# LCD_Disp_AIR_for3xOIL.net
KiCad netlist of a schematic drawn in EAGLE
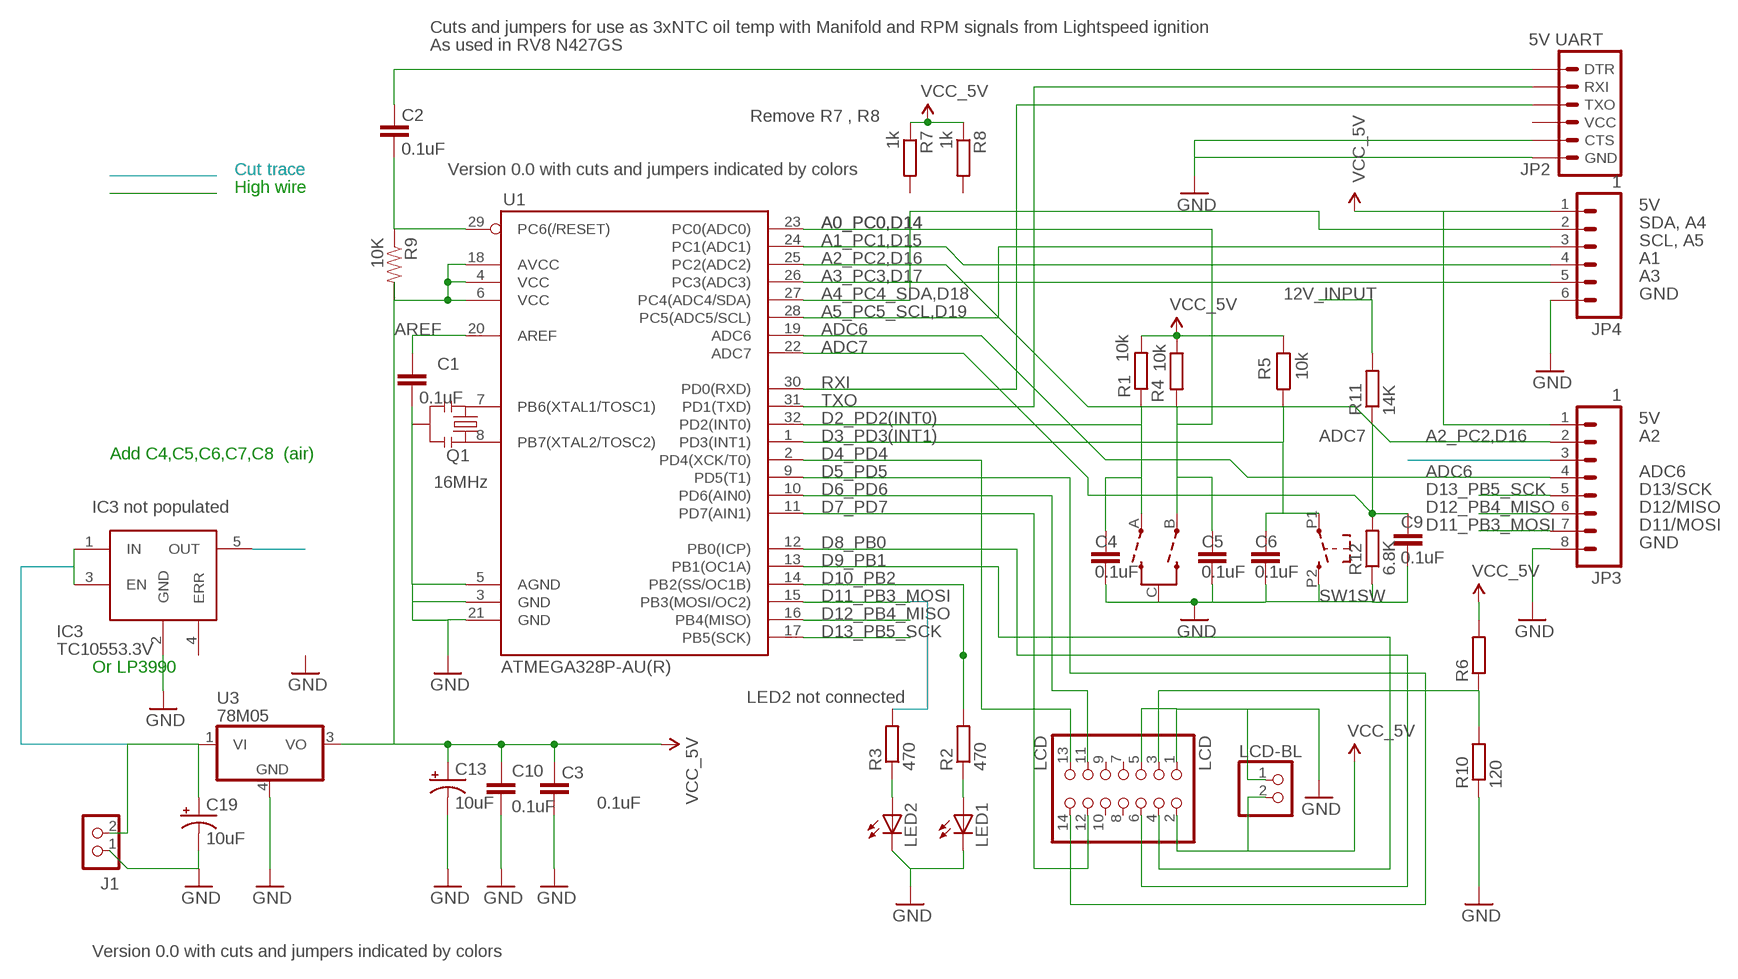
[diagram p0: schematic, sheet 1]

(export (version "E")
  (design (tool "Eeschema 10.0.6"))
  (components
    (comp (ref "C1")
      (value "0.1uF")
      (footprint "eagle-import:0805")
      (libsource (lib "eagle-import") (part "CAP0805"))
    )
    (comp (ref "C2")
      (value "0.1uF")
      (footprint "eagle-import:0805")
      (libsource (lib "eagle-import") (part "CAP0805"))
    )
    (comp (ref "C3")
      (value "0.1uF")
      (footprint "eagle-import:0805")
      (libsource (lib "eagle-import") (part "CAP0805"))
    )
    (comp (ref "C4")
      (value "0.1uF")
      (footprint "eagle-import:0805")
      (libsource (lib "eagle-import") (part "CAP0805"))
    )
    (comp (ref "C5")
      (value "0.1uF")
      (footprint "eagle-import:0805")
      (libsource (lib "eagle-import") (part "CAP0805"))
    )
    (comp (ref "C6")
      (value "0.1uF")
      (footprint "eagle-import:0805")
      (libsource (lib "eagle-import") (part "CAP0805"))
    )
    (comp (ref "C9")
      (value "0.1uF")
      (footprint "eagle-import:0805")
      (libsource (lib "eagle-import") (part "CAP0805"))
    )
    (comp (ref "C10")
      (value "0.1uF")
      (footprint "eagle-import:0805")
      (libsource (lib "eagle-import") (part "CAP0805"))
    )
    (comp (ref "C13")
      (value "10uF")
      (footprint "eagle-import:EIA3216")
      (libsource (lib "eagle-import") (part "CAP_POL1206"))
    )
    (comp (ref "C19")
      (value "10uF")
      (footprint "eagle-import:EIA7343")
      (libsource (lib "eagle-import") (part "CAP_POL7343"))
    )
    (comp (ref "IC3")
      (value "TC10553.3V")
      (footprint "eagle-import:SOT23-5")
      (libsource (lib "eagle-import") (part "TC10553.3V"))
    )
    (comp (ref "J1")
      (value "12V input")
      (footprint "eagle-import:M1X2")
      (libsource (lib "eagle-import") (part "CON_HEADER_1X02-PTH"))
    )
    (comp (ref "JP2")
      (value "5V UART")
      (footprint "eagle-import:1X06")
      (libsource (lib "eagle-import") (part "ARDUINO_SERIAL_PROGRAMPTH"))
    )
    (comp (ref "JP3")
      (value "1")
      (footprint "eagle-import:1X08")
      (libsource (lib "eagle-import") (part "M081X08"))
    )
    (comp (ref "JP4")
      (value "1")
      (footprint "eagle-import:1X06")
      (libsource (lib "eagle-import") (part "M06SIP"))
    )
    (comp (ref "LCD")
      (value "LCD")
      (footprint "eagle-import:2X07")
      (libsource (lib "eagle-import") (part "PINHD-2X7"))
    )
    (comp (ref "LCD-BL")
      (value "PINHD-1X2")
      (footprint "eagle-import:1X02")
      (libsource (lib "eagle-import") (part "PINHD-1X2"))
    )
    (comp (ref "LED1")
      (value "LED-5MM")
      (footprint "eagle-import:LED-5MM")
      (libsource (lib "eagle-import") (part "LED-5MM"))
    )
    (comp (ref "LED2")
      (value "LED-5MM")
      (footprint "eagle-import:LED-5MM")
      (libsource (lib "eagle-import") (part "LED-5MM"))
    )
    (comp (ref "Q1")
      (value "16MHz")
      (footprint "eagle-import:RESONATOR-SMD")
      (libsource (lib "eagle-import") (part "RESONATORSMD"))
    )
    (comp (ref "R1")
      (value "10k")
      (footprint "eagle-import:R603")
      (libsource (lib "eagle-import") (part "RESISTOR-0603"))
    )
    (comp (ref "R2")
      (value "470")
      (footprint "eagle-import:R603")
      (libsource (lib "eagle-import") (part "RESISTOR-0603"))
    )
    (comp (ref "R3")
      (value "470")
      (footprint "eagle-import:R603")
      (libsource (lib "eagle-import") (part "RESISTOR-0603"))
    )
    (comp (ref "R4")
      (value "10k")
      (footprint "eagle-import:R603")
      (libsource (lib "eagle-import") (part "RESISTOR-0603"))
    )
    (comp (ref "R5")
      (value "10k")
      (footprint "eagle-import:R603")
      (libsource (lib "eagle-import") (part "RESISTOR-0603"))
    )
    (comp (ref "R6")
      (value "RESISTOR-0603")
      (footprint "eagle-import:R603")
      (libsource (lib "eagle-import") (part "RESISTOR-0603"))
    )
    (comp (ref "R7")
      (value "1k")
      (footprint "eagle-import:R603")
      (libsource (lib "eagle-import") (part "RESISTOR-0603"))
    )
    (comp (ref "R8")
      (value "1k")
      (footprint "eagle-import:R603")
      (libsource (lib "eagle-import") (part "RESISTOR-0603"))
    )
    (comp (ref "R9")
      (value "10K")
      (footprint "eagle-import:0603")
      (libsource (lib "eagle-import") (part "RESISTOR0603"))
    )
    (comp (ref "R10")
      (value "120")
      (footprint "eagle-import:R603")
      (libsource (lib "eagle-import") (part "RESISTOR-0603"))
    )
    (comp (ref "R11")
      (value "14K")
      (footprint "eagle-import:R603")
      (libsource (lib "eagle-import") (part "RESISTOR-0603"))
    )
    (comp (ref "R12")
      (value "6.8K")
      (footprint "eagle-import:R603")
      (libsource (lib "eagle-import") (part "RESISTOR-0603"))
    )
    (comp (ref "SW1")
      (value "ENCODER_SW1-PEC12")
      (footprint "eagle-import:PEC12_INCREMENTAL_ENCODER")
      (libsource (lib "eagle-import") (part "ENCODER_SW1-PEC12"))
    )
    (comp (ref "U1")
      (value "ATMEGA328P-AU(R)")
      (footprint "eagle-import:TQFP32-08")
      (libsource (lib "eagle-import") (part "ATMEGA168"))
    )
    (comp (ref "U3")
      (value "78M05")
      (footprint "eagle-import:DPACK")
      (libsource (lib "eagle-import") (part "78MXXL"))
    )
  )
  (nets
    (net (code "1") (name "/12V_INPUT") (class "Default")
      (node (ref "C19") (pin "A") (pinfunction "+_A") (pintype "passive"))
      (node (ref "J1") (pin "2") (pinfunction "2_2") (pintype "passive"))
      (node (ref "R11") (pin "2") (pinfunction "2_2") (pintype "passive"))
      (node (ref "U3") (pin "1") (pinfunction "VI_1") (pintype "input"))
    )
    (net (code "2") (name "/A0_PC0,D14") (class "Default")
      (node (ref "C5") (pin "2") (pinfunction "2_2") (pintype "passive"))
      (node (ref "R4") (pin "2") (pinfunction "2_2") (pintype "passive"))
      (node (ref "SW1") (pin "B") (pinfunction "B_B") (pintype "passive"))
      (node (ref "U1") (pin "23") (pinfunction "PC0(ADC0)_23") (pintype "bidirectional"))
    )
    (net (code "3") (name "/A1_PC1,D15") (class "Default")
      (node (ref "JP4") (pin "4") (pinfunction "4_4") (pintype "passive"))
      (node (ref "U1") (pin "24") (pinfunction "PC1(ADC1)_24") (pintype "bidirectional"))
    )
    (net (code "4") (name "/A2_PC2,D16") (class "Default")
      (node (ref "JP3") (pin "2") (pinfunction "2_2") (pintype "passive"))
      (node (ref "U1") (pin "25") (pinfunction "PC2(ADC2)_25") (pintype "bidirectional"))
    )
    (net (code "5") (name "/A3_PC3,D17") (class "Default")
      (node (ref "JP4") (pin "5") (pinfunction "5_5") (pintype "passive"))
      (node (ref "U1") (pin "26") (pinfunction "PC3(ADC3)_26") (pintype "bidirectional"))
    )
    (net (code "6") (name "/A4_PC4_SDA,D18") (class "Default")
      (node (ref "JP4") (pin "2") (pinfunction "2_2") (pintype "passive"))
      (node (ref "U1") (pin "27") (pinfunction "PC4(ADC4/SDA)_27") (pintype "bidirectional"))
    )
    (net (code "7") (name "/A5_PC5_SCL,D19") (class "Default")
      (node (ref "JP4") (pin "3") (pinfunction "3_3") (pintype "passive"))
      (node (ref "U1") (pin "28") (pinfunction "PC5(ADC5/SCL)_28") (pintype "bidirectional"))
    )
    (net (code "8") (name "/ADC6") (class "Default")
      (node (ref "JP3") (pin "4") (pinfunction "4_4") (pintype "passive"))
      (node (ref "U1") (pin "19") (pinfunction "ADC6_19") (pintype "bidirectional"))
    )
    (net (code "9") (name "/ADC7") (class "Default")
      (node (ref "C9") (pin "1") (pinfunction "1_1") (pintype "passive"))
      (node (ref "R11") (pin "1") (pinfunction "1_1") (pintype "passive"))
      (node (ref "R12") (pin "2") (pinfunction "2_2") (pintype "passive"))
      (node (ref "U1") (pin "22") (pinfunction "ADC7_22") (pintype "bidirectional"))
    )
    (net (code "10") (name "/AREF") (class "Default")
      (node (ref "C1") (pin "2") (pinfunction "2_2") (pintype "passive"))
      (node (ref "U1") (pin "20") (pinfunction "AREF_20") (pintype "bidirectional"))
    )
    (net (code "11") (name "/D2_PD2(INT0)") (class "Default")
      (node (ref "C4") (pin "2") (pinfunction "2_2") (pintype "passive"))
      (node (ref "R1") (pin "1") (pinfunction "1_1") (pintype "passive"))
      (node (ref "SW1") (pin "A") (pinfunction "A_A") (pintype "passive"))
      (node (ref "U1") (pin "32") (pinfunction "PD2(INT0)_32") (pintype "bidirectional"))
    )
    (net (code "12") (name "/D3_PD3(INT1)") (class "Default")
      (node (ref "C6") (pin "2") (pinfunction "2_2") (pintype "passive"))
      (node (ref "R5") (pin "1") (pinfunction "1_1") (pintype "passive"))
      (node (ref "SW1") (pin "P1") (pinfunction "1_P1") (pintype "passive"))
      (node (ref "U1") (pin "1") (pinfunction "PD3(INT1)_1") (pintype "bidirectional"))
    )
    (net (code "13") (name "/D4_PD4") (class "Default")
      (node (ref "LCD") (pin "13") (pinfunction "13_13") (pintype "passive"))
      (node (ref "U1") (pin "2") (pinfunction "PD4(XCK/T0)_2") (pintype "bidirectional"))
    )
    (net (code "14") (name "/D5_PD5") (class "Default")
      (node (ref "LCD") (pin "14") (pinfunction "14_14") (pintype "passive"))
      (node (ref "U1") (pin "9") (pinfunction "PD5(T1)_9") (pintype "bidirectional"))
    )
    (net (code "15") (name "/D6_PD6") (class "Default")
      (node (ref "LCD") (pin "11") (pinfunction "11_11") (pintype "passive"))
      (node (ref "U1") (pin "10") (pinfunction "PD6(AIN0)_10") (pintype "bidirectional"))
    )
    (net (code "16") (name "/D7_PD7") (class "Default")
      (node (ref "LCD") (pin "12") (pinfunction "12_12") (pintype "passive"))
      (node (ref "U1") (pin "11") (pinfunction "PD7(AIN1)_11") (pintype "bidirectional"))
    )
    (net (code "17") (name "/D8_PB0") (class "Default")
      (node (ref "LCD") (pin "6") (pinfunction "6_6") (pintype "passive"))
      (node (ref "U1") (pin "12") (pinfunction "PB0(ICP)_12") (pintype "bidirectional"))
    )
    (net (code "18") (name "/D9_PB1") (class "Default")
      (node (ref "LCD") (pin "4") (pinfunction "4_4") (pintype "passive"))
      (node (ref "U1") (pin "13") (pinfunction "PB1(OC1A)_13") (pintype "bidirectional"))
    )
    (net (code "19") (name "/D10_PB2") (class "Default")
      (node (ref "R2") (pin "2") (pinfunction "2_2") (pintype "passive"))
      (node (ref "U1") (pin "14") (pinfunction "PB2(SS/OC1B)_14") (pintype "bidirectional"))
    )
    (net (code "20") (name "/D11_PB3_MOSI") (class "Default")
      (node (ref "JP3") (pin "7") (pinfunction "7_7") (pintype "passive"))
      (node (ref "U1") (pin "15") (pinfunction "PB3(MOSI/OC2)_15") (pintype "bidirectional"))
    )
    (net (code "21") (name "/D12_PB4_MISO") (class "Default")
      (node (ref "JP3") (pin "6") (pinfunction "6_6") (pintype "passive"))
      (node (ref "U1") (pin "16") (pinfunction "PB4(MISO)_16") (pintype "bidirectional"))
    )
    (net (code "22") (name "/D13_PB5_SCK") (class "Default")
      (node (ref "JP3") (pin "5") (pinfunction "5_5") (pintype "passive"))
      (node (ref "U1") (pin "17") (pinfunction "PB5(SCK)_17") (pintype "bidirectional"))
    )
    (net (code "23") (name "/OUT") (class "Default")
      (node (ref "IC3") (pin "5") (pinfunction "OUT_5") (pintype "power_in"))
    )
    (net (code "24") (name "/RXI") (class "Default")
      (node (ref "JP2") (pin "3") (pinfunction "TXO_3") (pintype "passive"))
      (node (ref "U1") (pin "30") (pinfunction "PD0(RXD)_30") (pintype "bidirectional"))
    )
    (net (code "25") (name "/TXO") (class "Default")
      (node (ref "JP2") (pin "2") (pinfunction "RXI_2") (pintype "passive"))
      (node (ref "U1") (pin "31") (pinfunction "PD1(TXD)_31") (pintype "bidirectional"))
    )
    (net (code "26") (name "GND") (class "Default")
      (node (ref "C1") (pin "1") (pinfunction "1_1") (pintype "passive"))
      (node (ref "C10") (pin "2") (pinfunction "2_2") (pintype "passive"))
      (node (ref "C13") (pin "C") (pinfunction "-_C") (pintype "passive"))
      (node (ref "C19") (pin "C") (pinfunction "-_C") (pintype "passive"))
      (node (ref "C3") (pin "1") (pinfunction "1_1") (pintype "passive"))
      (node (ref "C4") (pin "1") (pinfunction "1_1") (pintype "passive"))
      (node (ref "C5") (pin "1") (pinfunction "1_1") (pintype "passive"))
      (node (ref "C6") (pin "1") (pinfunction "1_1") (pintype "passive"))
      (node (ref "C9") (pin "2") (pinfunction "2_2") (pintype "passive"))
      (node (ref "IC3") (pin "2") (pinfunction "GND_2") (pintype "power_in"))
      (node (ref "J1") (pin "1") (pinfunction "1_1") (pintype "passive"))
      (node (ref "JP2") (pin "5") (pinfunction "CTS_5") (pintype "passive"))
      (node (ref "JP2") (pin "6") (pinfunction "GND_6") (pintype "passive"))
      (node (ref "JP3") (pin "8") (pinfunction "8_8") (pintype "passive"))
      (node (ref "JP4") (pin "6") (pinfunction "6_6") (pintype "passive"))
      (node (ref "LCD") (pin "1") (pinfunction "1_1") (pintype "passive"))
      (node (ref "LCD") (pin "5") (pinfunction "5_5") (pintype "passive"))
      (node (ref "LCD-BL") (pin "1") (pinfunction "1_1") (pintype "passive"))
      (node (ref "LED1") (pin "K") (pinfunction "C_K") (pintype "passive"))
      (node (ref "LED2") (pin "K") (pinfunction "C_K") (pintype "passive"))
      (node (ref "Q1") (pin "2") (pinfunction "2_2") (pintype "passive"))
      (node (ref "R10") (pin "1") (pinfunction "1_1") (pintype "passive"))
      (node (ref "R12") (pin "1") (pinfunction "1_1") (pintype "passive"))
      (node (ref "SW1") (pin "C") (pinfunction "C_C") (pintype "passive"))
      (node (ref "SW1") (pin "P2") (pinfunction "2_P2") (pintype "passive"))
      (node (ref "U1") (pin "21") (pinfunction "GND_21") (pintype "bidirectional"))
      (node (ref "U1") (pin "3") (pinfunction "GND_3") (pintype "bidirectional"))
      (node (ref "U1") (pin "5") (pinfunction "AGND_5") (pintype "bidirectional"))
      (node (ref "U3") (pin "4") (pinfunction "GND_4") (pintype "passive"))
    )
    (net (code "27") (name "Net-(IC3-EN)") (class "Default")
      (node (ref "IC3") (pin "1") (pinfunction "IN_1") (pintype "power_in"))
      (node (ref "IC3") (pin "3") (pinfunction "EN_3") (pintype "input"))
    )
    (net (code "28") (name "Net-(JP2-DTR)") (class "Default")
      (node (ref "C2") (pin "2") (pinfunction "2_2") (pintype "passive"))
      (node (ref "JP2") (pin "1") (pinfunction "DTR_1") (pintype "passive"))
    )
    (net (code "29") (name "Net-(LCD-Pad3)") (class "Default")
      (node (ref "LCD") (pin "3") (pinfunction "3_3") (pintype "passive"))
      (node (ref "R10") (pin "2") (pinfunction "2_2") (pintype "passive"))
      (node (ref "R6") (pin "1") (pinfunction "1_1") (pintype "passive"))
    )
    (net (code "30") (name "Net-(LED1-PadA)") (class "Default")
      (node (ref "LED1") (pin "A") (pinfunction "A_A") (pintype "passive"))
      (node (ref "R2") (pin "1") (pinfunction "1_1") (pintype "passive"))
    )
    (net (code "31") (name "Net-(LED2-PadA)") (class "Default")
      (node (ref "LED2") (pin "A") (pinfunction "A_A") (pintype "passive"))
      (node (ref "R3") (pin "1") (pinfunction "1_1") (pintype "passive"))
    )
    (net (code "32") (name "Net-(U1-PB6(XTAL1{slash}TOSC1))") (class "Default")
      (node (ref "Q1") (pin "3") (pinfunction "3_3") (pintype "passive"))
      (node (ref "U1") (pin "7") (pinfunction "PB6(XTAL1/TOSC1)_7") (pintype "bidirectional"))
    )
    (net (code "33") (name "Net-(U1-PB7(XTAL2{slash}TOSC2))") (class "Default")
      (node (ref "Q1") (pin "1") (pinfunction "1_1") (pintype "passive"))
      (node (ref "U1") (pin "8") (pinfunction "PB7(XTAL2/TOSC2)_8") (pintype "bidirectional"))
    )
    (net (code "34") (name "Net-(U1-PC6({slash}RESET))") (class "Default")
      (node (ref "C2") (pin "1") (pinfunction "1_1") (pintype "passive"))
      (node (ref "R9") (pin "1") (pinfunction "1_1") (pintype "passive"))
      (node (ref "U1") (pin "29") (pinfunction "PC6(/RESET)_29") (pintype "bidirectional"))
    )
    (net (code "35") (name "VCC_5V") (class "Default")
      (node (ref "C10") (pin "1") (pinfunction "1_1") (pintype "passive"))
      (node (ref "C13") (pin "A") (pinfunction "+_A") (pintype "passive"))
      (node (ref "C3") (pin "2") (pinfunction "2_2") (pintype "passive"))
      (node (ref "JP3") (pin "1") (pinfunction "1_1") (pintype "passive"))
      (node (ref "JP4") (pin "1") (pinfunction "1_1") (pintype "passive"))
      (node (ref "LCD") (pin "2") (pinfunction "2_2") (pintype "passive"))
      (node (ref "LCD-BL") (pin "2") (pinfunction "2_2") (pintype "passive"))
      (node (ref "R1") (pin "2") (pinfunction "2_2") (pintype "passive"))
      (node (ref "R4") (pin "1") (pinfunction "1_1") (pintype "passive"))
      (node (ref "R5") (pin "2") (pinfunction "2_2") (pintype "passive"))
      (node (ref "R6") (pin "2") (pinfunction "2_2") (pintype "passive"))
      (node (ref "R7") (pin "1") (pinfunction "1_1") (pintype "passive"))
      (node (ref "R8") (pin "1") (pinfunction "1_1") (pintype "passive"))
      (node (ref "R9") (pin "2") (pinfunction "2_2") (pintype "passive"))
      (node (ref "U1") (pin "18") (pinfunction "AVCC_18") (pintype "bidirectional"))
      (node (ref "U1") (pin "4") (pinfunction "VCC_4") (pintype "bidirectional"))
      (node (ref "U1") (pin "6") (pinfunction "VCC_6") (pintype "bidirectional"))
      (node (ref "U3") (pin "3") (pinfunction "VO_3") (pintype "passive"))
    )
    (net (code "36") (name "unconnected-(IC3-ERR-Pad4)") (class "Default")
      (node (ref "IC3") (pin "4") (pinfunction "ERR_4") (pintype "output"))
    )
    (net (code "37") (name "unconnected-(JP2-VCC-Pad4)") (class "Default")
      (node (ref "JP2") (pin "4") (pinfunction "VCC_4") (pintype "passive"))
    )
    (net (code "38") (name "unconnected-(JP3-Pad3)") (class "Default")
      (node (ref "JP3") (pin "3") (pinfunction "3_3") (pintype "passive"))
    )
    (net (code "39") (name "unconnected-(LCD-Pad7)") (class "Default")
      (node (ref "LCD") (pin "7") (pinfunction "7_7") (pintype "passive"))
    )
    (net (code "40") (name "unconnected-(LCD-Pad8)") (class "Default")
      (node (ref "LCD") (pin "8") (pinfunction "8_8") (pintype "passive"))
    )
    (net (code "41") (name "unconnected-(LCD-Pad9)") (class "Default")
      (node (ref "LCD") (pin "9") (pinfunction "9_9") (pintype "passive"))
    )
    (net (code "42") (name "unconnected-(LCD-Pad10)") (class "Default")
      (node (ref "LCD") (pin "10") (pinfunction "10_10") (pintype "passive"))
    )
    (net (code "43") (name "unconnected-(R3-Pad2)") (class "Default")
      (node (ref "R3") (pin "2") (pinfunction "2_2") (pintype "passive"))
    )
    (net (code "44") (name "unconnected-(R7-Pad2)") (class "Default")
      (node (ref "R7") (pin "2") (pinfunction "2_2") (pintype "passive"))
    )
    (net (code "45") (name "unconnected-(R8-Pad2)") (class "Default")
      (node (ref "R8") (pin "2") (pinfunction "2_2") (pintype "passive"))
    )
  )
)
